# LoRa_Mini_v1_3.net
KiCad netlist of a schematic drawn in EAGLE
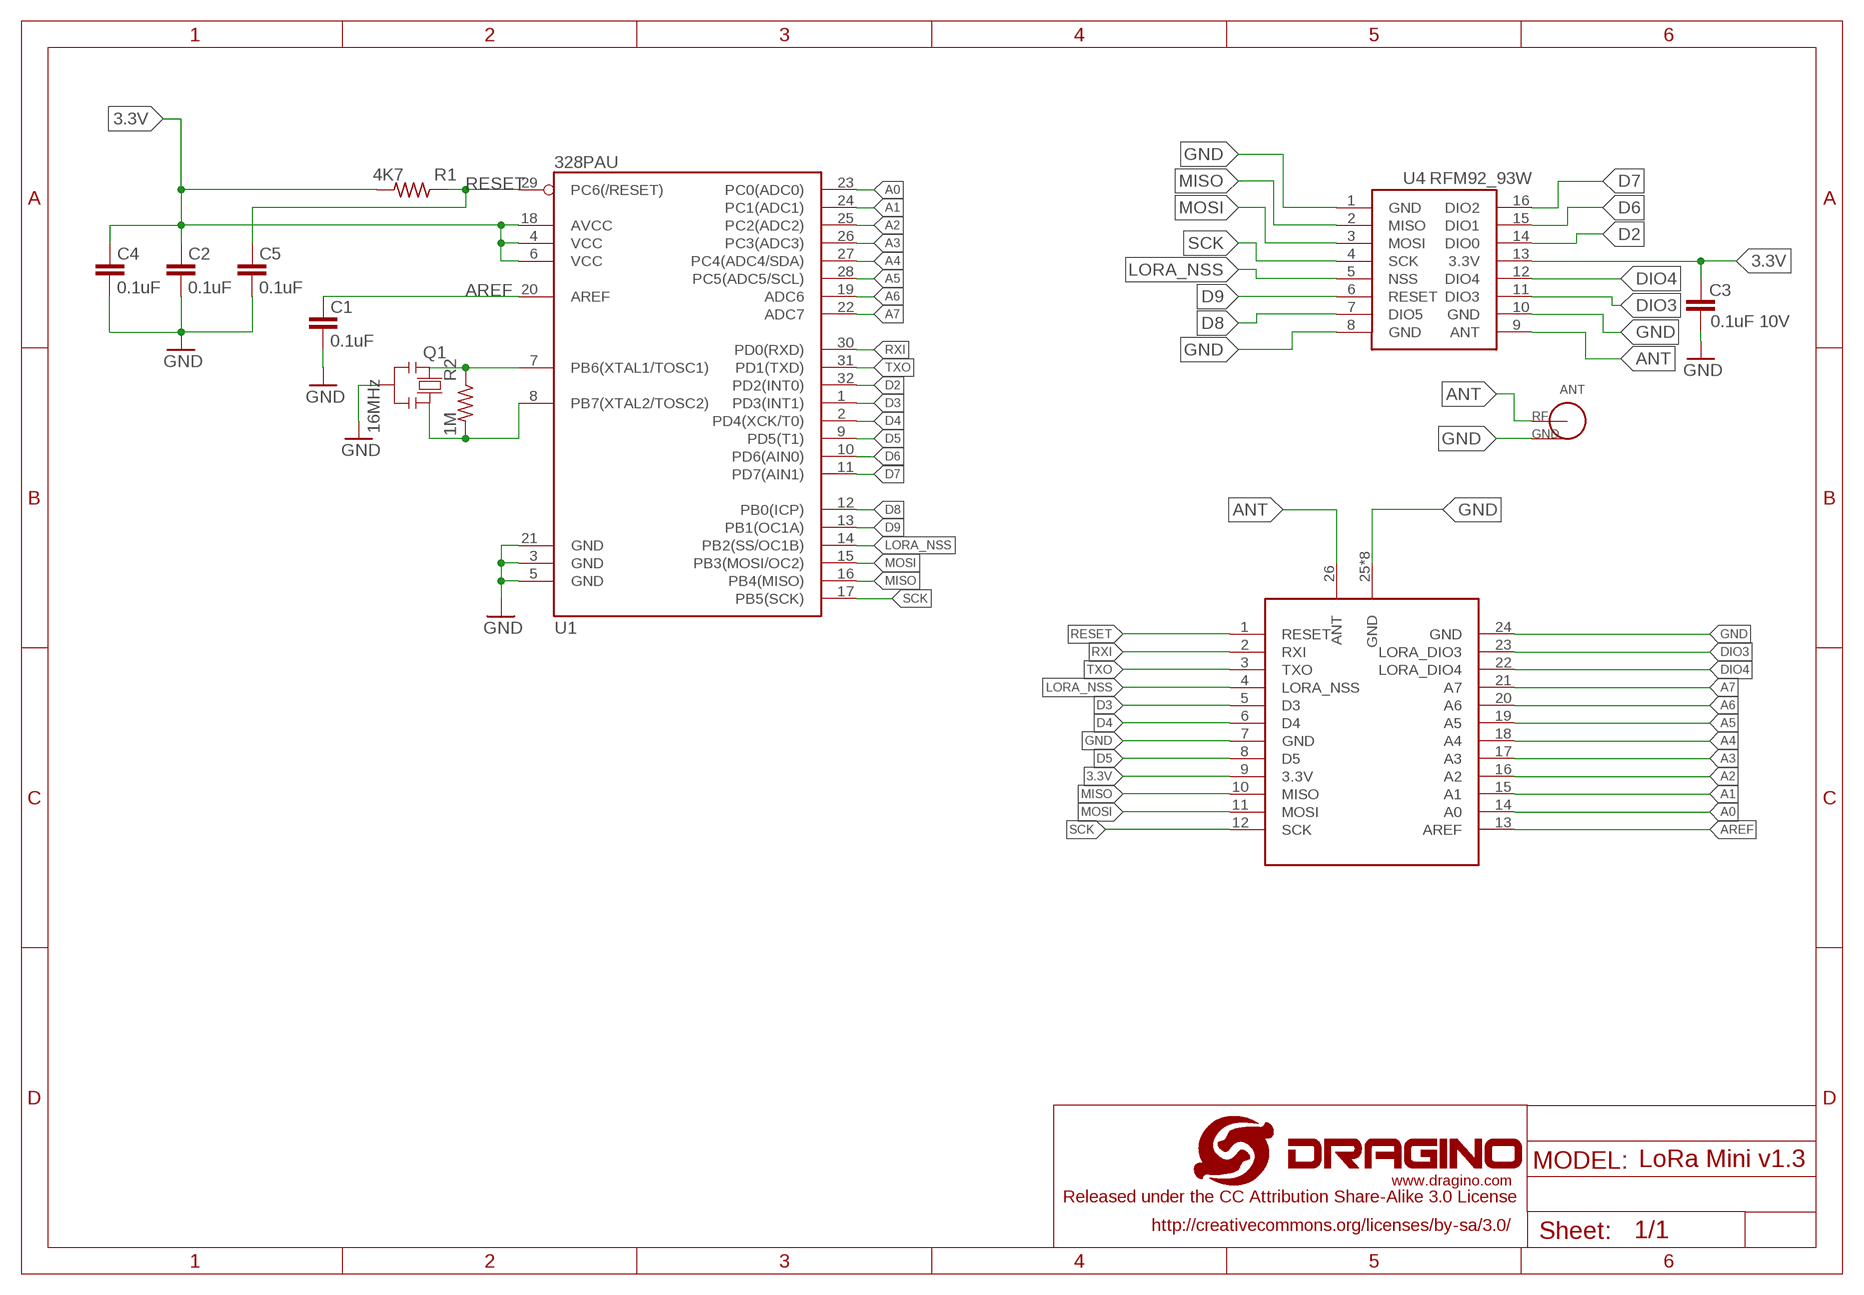
[diagram p0: schematic, sheet 1]

(export (version "E")
  (design (tool "Eeschema 10.0.6"))
  (components
    (comp (ref "ANT")
      (value "I-PEX")
      (footprint "eagle-import:I-PEX")
      (libsource (lib "eagle-import") (part "I-PEX"))
    )
    (comp (ref "C1")
      (value "0.1uF")
      (footprint "eagle-import:C0402")
      (libsource (lib "eagle-import") (part "C-EUC0402"))
    )
    (comp (ref "C2")
      (value "0.1uF")
      (footprint "eagle-import:C0402")
      (libsource (lib "eagle-import") (part "C-EUC0402"))
    )
    (comp (ref "C3")
      (value "0.1uF 10V")
      (footprint "eagle-import:C0402")
      (libsource (lib "eagle-import") (part "C-EUC0402"))
    )
    (comp (ref "C4")
      (value "0.1uF")
      (footprint "eagle-import:C0402")
      (libsource (lib "eagle-import") (part "C-EUC0402"))
    )
    (comp (ref "C5")
      (value "0.1uF")
      (footprint "eagle-import:C0402")
      (libsource (lib "eagle-import") (part "C-EUC0402"))
    )
    (comp (ref "Q1")
      (value "16MHz")
      (footprint "eagle-import:RESONATOR")
      (libsource (lib "eagle-import") (part "RESONATORMU"))
    )
    (comp (ref "R1")
      (value "4K7")
      (footprint "eagle-import:R0402")
      (libsource (lib "eagle-import") (part "R-US_R0402"))
    )
    (comp (ref "R2")
      (value "1M")
      (footprint "eagle-import:R0402")
      (libsource (lib "eagle-import") (part "R-US_R0402"))
    )
    (comp (ref "U$1")
      (value "LORA328P_PCB")
      (footprint "eagle-import:LORA328P_PCB")
      (libsource (lib "eagle-import") (part "LORA328P_PCB"))
    )
    (comp (ref "U1")
      (value "328PAU")
      (footprint "eagle-import:328PAU")
      (libsource (lib "eagle-import") (part "328PAU"))
    )
    (comp (ref "U4")
      (value "RFM92_93W")
      (footprint "eagle-import:RFM92_93W")
      (libsource (lib "eagle-import") (part "RFM92_93W"))
    )
  )
  (nets
    (net (code "1") (name "3.3V") (class "Default")
      (node (ref "C2") (pin "2") (pinfunction "2_2") (pintype "passive"))
      (node (ref "C3") (pin "2") (pinfunction "2_2") (pintype "passive"))
      (node (ref "C4") (pin "2") (pinfunction "2_2") (pintype "passive"))
      (node (ref "R1") (pin "2") (pinfunction "2_2") (pintype "passive"))
      (node (ref "U$1") (pin "9") (pinfunction "3.3V_9") (pintype "bidirectional"))
      (node (ref "U1") (pin "18") (pinfunction "AVCC_18") (pintype "bidirectional"))
      (node (ref "U1") (pin "4") (pinfunction "VCC_4") (pintype "bidirectional"))
      (node (ref "U1") (pin "6") (pinfunction "VCC_6") (pintype "bidirectional"))
      (node (ref "U4") (pin "13") (pinfunction "3.3V_13") (pintype "power_in"))
    )
    (net (code "2") (name "A0") (class "Default")
      (node (ref "U$1") (pin "14") (pinfunction "A0_14") (pintype "bidirectional"))
      (node (ref "U1") (pin "23") (pinfunction "PC0(ADC0)_23") (pintype "bidirectional"))
    )
    (net (code "3") (name "A1") (class "Default")
      (node (ref "U$1") (pin "15") (pinfunction "A1_15") (pintype "bidirectional"))
      (node (ref "U1") (pin "24") (pinfunction "PC1(ADC1)_24") (pintype "bidirectional"))
    )
    (net (code "4") (name "A2") (class "Default")
      (node (ref "U$1") (pin "16") (pinfunction "A2_16") (pintype "bidirectional"))
      (node (ref "U1") (pin "25") (pinfunction "PC2(ADC2)_25") (pintype "bidirectional"))
    )
    (net (code "5") (name "A3") (class "Default")
      (node (ref "U$1") (pin "17") (pinfunction "A3_17") (pintype "bidirectional"))
      (node (ref "U1") (pin "26") (pinfunction "PC3(ADC3)_26") (pintype "bidirectional"))
    )
    (net (code "6") (name "A4") (class "Default")
      (node (ref "U$1") (pin "18") (pinfunction "A4_18") (pintype "bidirectional"))
      (node (ref "U1") (pin "27") (pinfunction "PC4(ADC4/SDA)_27") (pintype "bidirectional"))
    )
    (net (code "7") (name "A5") (class "Default")
      (node (ref "U$1") (pin "19") (pinfunction "A5_19") (pintype "bidirectional"))
      (node (ref "U1") (pin "28") (pinfunction "PC5(ADC5/SCL)_28") (pintype "bidirectional"))
    )
    (net (code "8") (name "A6") (class "Default")
      (node (ref "U$1") (pin "20") (pinfunction "A6_20") (pintype "bidirectional"))
      (node (ref "U1") (pin "19") (pinfunction "ADC6_19") (pintype "bidirectional"))
    )
    (net (code "9") (name "A7") (class "Default")
      (node (ref "U$1") (pin "21") (pinfunction "A7_21") (pintype "bidirectional"))
      (node (ref "U1") (pin "22") (pinfunction "ADC7_22") (pintype "bidirectional"))
    )
    (net (code "10") (name "ANT") (class "Default")
      (node (ref "ANT") (pin "SIG") (pinfunction "SIG_SIG") (pintype "passive"))
      (node (ref "U$1") (pin "26") (pinfunction "ANT_26") (pintype "bidirectional"))
      (node (ref "U4") (pin "9") (pinfunction "ANT_9") (pintype "bidirectional"))
    )
    (net (code "11") (name "AREF") (class "Default")
      (node (ref "C1") (pin "2") (pinfunction "2_2") (pintype "passive"))
      (node (ref "U$1") (pin "13") (pinfunction "AREF_13") (pintype "bidirectional"))
      (node (ref "U1") (pin "20") (pinfunction "AREF_20") (pintype "bidirectional"))
    )
    (net (code "12") (name "D2") (class "Default")
      (node (ref "U1") (pin "32") (pinfunction "PD2(INT0)_32") (pintype "bidirectional"))
      (node (ref "U4") (pin "14") (pinfunction "DIO0_14") (pintype "bidirectional"))
    )
    (net (code "13") (name "D3") (class "Default")
      (node (ref "U$1") (pin "5") (pinfunction "D3_5") (pintype "bidirectional"))
      (node (ref "U1") (pin "1") (pinfunction "PD3(INT1)_1") (pintype "bidirectional"))
    )
    (net (code "14") (name "D4") (class "Default")
      (node (ref "U$1") (pin "6") (pinfunction "D4_6") (pintype "bidirectional"))
      (node (ref "U1") (pin "2") (pinfunction "PD4(XCK/T0)_2") (pintype "bidirectional"))
    )
    (net (code "15") (name "D5") (class "Default")
      (node (ref "U$1") (pin "8") (pinfunction "D5_8") (pintype "bidirectional"))
      (node (ref "U1") (pin "9") (pinfunction "PD5(T1)_9") (pintype "bidirectional"))
    )
    (net (code "16") (name "D6") (class "Default")
      (node (ref "U1") (pin "10") (pinfunction "PD6(AIN0)_10") (pintype "bidirectional"))
      (node (ref "U4") (pin "15") (pinfunction "DIO1_15") (pintype "bidirectional"))
    )
    (net (code "17") (name "D7") (class "Default")
      (node (ref "U1") (pin "11") (pinfunction "PD7(AIN1)_11") (pintype "bidirectional"))
      (node (ref "U4") (pin "16") (pinfunction "DIO2_16") (pintype "bidirectional"))
    )
    (net (code "18") (name "D8") (class "Default")
      (node (ref "U1") (pin "12") (pinfunction "PB0(ICP)_12") (pintype "bidirectional"))
      (node (ref "U4") (pin "7") (pinfunction "DIO5_7") (pintype "bidirectional"))
    )
    (net (code "19") (name "D9") (class "Default")
      (node (ref "U1") (pin "13") (pinfunction "PB1(OC1A)_13") (pintype "bidirectional"))
      (node (ref "U4") (pin "6") (pinfunction "RESET_6") (pintype "bidirectional"))
    )
    (net (code "20") (name "DIO3") (class "Default")
      (node (ref "U$1") (pin "23") (pinfunction "LORA_DIO3_23") (pintype "bidirectional"))
      (node (ref "U4") (pin "11") (pinfunction "DIO3_11") (pintype "bidirectional"))
    )
    (net (code "21") (name "DIO4") (class "Default")
      (node (ref "U$1") (pin "22") (pinfunction "LORA_DIO4_22") (pintype "bidirectional"))
      (node (ref "U4") (pin "12") (pinfunction "DIO4_12") (pintype "bidirectional"))
    )
    (net (code "22") (name "GND") (class "Default")
      (node (ref "ANT") (pin "GND") (pinfunction "GND_GND") (pintype "passive"))
      (node (ref "ANT") (pin "GND1") (pinfunction "GND_GND1") (pintype "passive"))
      (node (ref "C1") (pin "1") (pinfunction "1_1") (pintype "passive"))
      (node (ref "C2") (pin "1") (pinfunction "1_1") (pintype "passive"))
      (node (ref "C3") (pin "1") (pinfunction "1_1") (pintype "passive"))
      (node (ref "C4") (pin "1") (pinfunction "1_1") (pintype "passive"))
      (node (ref "C5") (pin "1") (pinfunction "1_1") (pintype "passive"))
      (node (ref "Q1") (pin "2") (pinfunction "2_2") (pintype "passive"))
      (node (ref "U$1") (pin "24") (pinfunction "GND_24") (pintype "bidirectional"))
      (node (ref "U$1") (pin "25") (pinfunction "GND_25") (pintype "bidirectional"))
      (node (ref "U$1") (pin "7") (pinfunction "GND_7") (pintype "bidirectional"))
      (node (ref "U$1") (pin "P$1") (pinfunction "GND_P$1") (pintype "bidirectional"))
      (node (ref "U$1") (pin "P$2") (pinfunction "GND_P$2") (pintype "bidirectional"))
      (node (ref "U$1") (pin "P$3") (pinfunction "GND_P$3") (pintype "bidirectional"))
      (node (ref "U$1") (pin "P$4") (pinfunction "GND_P$4") (pintype "bidirectional"))
      (node (ref "U$1") (pin "P$5") (pinfunction "GND_P$5") (pintype "bidirectional"))
      (node (ref "U$1") (pin "P$6") (pinfunction "GND_P$6") (pintype "bidirectional"))
      (node (ref "U$1") (pin "P$7") (pinfunction "GND_P$7") (pintype "bidirectional"))
      (node (ref "U1") (pin "21") (pinfunction "GND_21") (pintype "bidirectional"))
      (node (ref "U1") (pin "3") (pinfunction "GND_3") (pintype "bidirectional"))
      (node (ref "U1") (pin "5") (pinfunction "GND_5") (pintype "bidirectional"))
      (node (ref "U4") (pin "1") (pinfunction "GND_1") (pintype "power_in"))
      (node (ref "U4") (pin "10") (pinfunction "GND_10") (pintype "power_in"))
      (node (ref "U4") (pin "8") (pinfunction "GND_8") (pintype "power_in"))
    )
    (net (code "23") (name "LORA_NSS") (class "Default")
      (node (ref "U$1") (pin "4") (pinfunction "LORA_NSS_4") (pintype "bidirectional"))
      (node (ref "U1") (pin "14") (pinfunction "PB2(SS/OC1B)_14") (pintype "bidirectional"))
      (node (ref "U4") (pin "5") (pinfunction "NSS_5") (pintype "bidirectional"))
    )
    (net (code "24") (name "MISO") (class "Default")
      (node (ref "U$1") (pin "10") (pinfunction "MISO_10") (pintype "bidirectional"))
      (node (ref "U1") (pin "16") (pinfunction "PB4(MISO)_16") (pintype "bidirectional"))
      (node (ref "U4") (pin "2") (pinfunction "MISO_2") (pintype "bidirectional"))
    )
    (net (code "25") (name "MOSI") (class "Default")
      (node (ref "U$1") (pin "11") (pinfunction "MOSI_11") (pintype "bidirectional"))
      (node (ref "U1") (pin "15") (pinfunction "PB3(MOSI/OC2)_15") (pintype "bidirectional"))
      (node (ref "U4") (pin "3") (pinfunction "MOSI_3") (pintype "bidirectional"))
    )
    (net (code "26") (name "Net-(U1-PB6(XTAL1{slash}TOSC1))") (class "Default")
      (node (ref "Q1") (pin "1") (pinfunction "1_1") (pintype "passive"))
      (node (ref "R2") (pin "1") (pinfunction "1_1") (pintype "passive"))
      (node (ref "U1") (pin "7") (pinfunction "PB6(XTAL1/TOSC1)_7") (pintype "bidirectional"))
    )
    (net (code "27") (name "Net-(U1-PB7(XTAL2{slash}TOSC2))") (class "Default")
      (node (ref "Q1") (pin "3") (pinfunction "3_3") (pintype "passive"))
      (node (ref "R2") (pin "2") (pinfunction "2_2") (pintype "passive"))
      (node (ref "U1") (pin "8") (pinfunction "PB7(XTAL2/TOSC2)_8") (pintype "bidirectional"))
    )
    (net (code "28") (name "RESET") (class "Default")
      (node (ref "C5") (pin "2") (pinfunction "2_2") (pintype "passive"))
      (node (ref "R1") (pin "1") (pinfunction "1_1") (pintype "passive"))
      (node (ref "U$1") (pin "1") (pinfunction "RESET_1") (pintype "bidirectional"))
      (node (ref "U1") (pin "29") (pinfunction "PC6(/RESET)_29") (pintype "bidirectional"))
    )
    (net (code "29") (name "RXI") (class "Default")
      (node (ref "U$1") (pin "2") (pinfunction "RXI_2") (pintype "bidirectional"))
      (node (ref "U1") (pin "30") (pinfunction "PD0(RXD)_30") (pintype "bidirectional"))
    )
    (net (code "30") (name "SCK") (class "Default")
      (node (ref "U$1") (pin "12") (pinfunction "SCK_12") (pintype "bidirectional"))
      (node (ref "U1") (pin "17") (pinfunction "PB5(SCK)_17") (pintype "bidirectional"))
      (node (ref "U4") (pin "4") (pinfunction "SCK_4") (pintype "bidirectional"))
    )
    (net (code "31") (name "TXO") (class "Default")
      (node (ref "U$1") (pin "3") (pinfunction "TXO_3") (pintype "bidirectional"))
      (node (ref "U1") (pin "31") (pinfunction "PD1(TXD)_31") (pintype "bidirectional"))
    )
  )
)
